# Sodonguyenly.net
KiCad netlist of a schematic drawn in Altium Designer
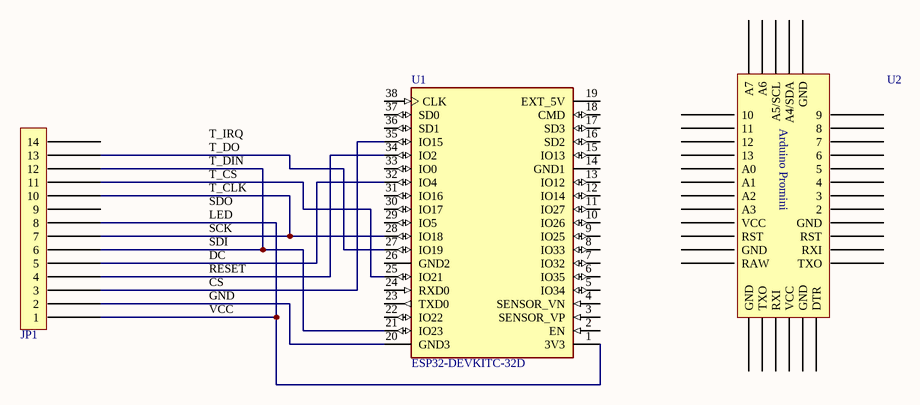
[diagram p0: Sodonguyenly.SchDoc]

(export (version "E")
  (design (tool "Eeschema 10.0.6"))
  (components
    (comp (ref "JP1")
      (value "JP")
      (footprint "Jumper 14x1 - duplicate")
      (libsource (lib "Thu vien jumper compoment") (part "Jumper 14x1"))
    )
    (comp (ref "U1")
      (value "ESP32-DEVKITC-32D")
      (footprint "MODULE_ESP32-DEVKITC-32D")
      (description "EVAL BOARD FOR ESP-WROOM-32")
      (fields (field (name "MF") "Espressif Systems"))
      (libsource (lib "ESP32-DEVKITC-32D") (part "ESP32-DEVKITC-32D"))
    )
    (comp (ref "U2")
      (value "Arduino Promini")
      (footprint "Arduino_Promini")
      (libsource (lib "Arduino_Promini") (part "Arduino Promini"))
    )
  )
  (nets
    (net (code "1") (name "Net-(U1-3V3)") (class "Default")
      (node (ref "JP1") (pin "1") (pinfunction "1_1") (pintype "passive"))
      (node (ref "JP1") (pin "8") (pinfunction "8_8") (pintype "passive"))
      (node (ref "U1") (pin "1") (pinfunction "3V3_1") (pintype "power_in"))
    )
    (net (code "2") (name "Net-(U1-GND3)") (class "Default")
      (node (ref "JP1") (pin "2") (pinfunction "2_2") (pintype "passive"))
      (node (ref "U1") (pin "20") (pinfunction "GND3_20") (pintype "power_in"))
    )
    (net (code "3") (name "Net-(U1-IO2)") (class "Default")
      (node (ref "JP1") (pin "4") (pinfunction "4_4") (pintype "passive"))
      (node (ref "U1") (pin "34") (pinfunction "IO2_34") (pintype "bidirectional"))
    )
    (net (code "4") (name "Net-(U1-IO4)") (class "Default")
      (node (ref "JP1") (pin "5") (pinfunction "5_5") (pintype "passive"))
      (node (ref "U1") (pin "32") (pinfunction "IO4_32") (pintype "bidirectional"))
    )
    (net (code "5") (name "Net-(U1-IO15)") (class "Default")
      (node (ref "JP1") (pin "3") (pinfunction "3_3") (pintype "passive"))
      (node (ref "U1") (pin "35") (pinfunction "IO15_35") (pintype "bidirectional"))
    )
    (net (code "6") (name "Net-(U1-IO18)") (class "Default")
      (node (ref "JP1") (pin "10") (pinfunction "10_10") (pintype "passive"))
      (node (ref "JP1") (pin "7") (pinfunction "7_7") (pintype "passive"))
      (node (ref "U1") (pin "28") (pinfunction "IO18_28") (pintype "bidirectional"))
    )
    (net (code "7") (name "Net-(U1-IO19)") (class "Default")
      (node (ref "JP1") (pin "13") (pinfunction "13_13") (pintype "passive"))
      (node (ref "U1") (pin "27") (pinfunction "IO19_27") (pintype "bidirectional"))
    )
    (net (code "8") (name "Net-(U1-IO21)") (class "Default")
      (node (ref "JP1") (pin "11") (pinfunction "11_11") (pintype "passive"))
      (node (ref "U1") (pin "25") (pinfunction "IO21_25") (pintype "bidirectional"))
    )
    (net (code "9") (name "Net-(U1-IO23)") (class "Default")
      (node (ref "JP1") (pin "12") (pinfunction "12_12") (pintype "passive"))
      (node (ref "JP1") (pin "6") (pinfunction "6_6") (pintype "passive"))
      (node (ref "U1") (pin "21") (pinfunction "IO23_21") (pintype "bidirectional"))
    )
    (net (code "10") (name "unconnected-(JP1-Pad9)") (class "Default")
      (node (ref "JP1") (pin "9") (pinfunction "9_9") (pintype "passive"))
    )
    (net (code "11") (name "unconnected-(JP1-Pad14)") (class "Default")
      (node (ref "JP1") (pin "14") (pinfunction "14_14") (pintype "passive"))
    )
    (net (code "12") (name "unconnected-(U1-CLK-Pad38)") (class "Default")
      (node (ref "U1") (pin "38") (pinfunction "CLK_38") (pintype "input"))
    )
    (net (code "13") (name "unconnected-(U1-CMD-Pad18)") (class "Default")
      (node (ref "U1") (pin "18") (pinfunction "CMD_18") (pintype "bidirectional"))
    )
    (net (code "14") (name "unconnected-(U1-EN-Pad2)") (class "Default")
      (node (ref "U1") (pin "2") (pinfunction "EN_2") (pintype "input"))
    )
    (net (code "15") (name "unconnected-(U1-EXT_5V-Pad19)") (class "Default")
      (node (ref "U1") (pin "19") (pinfunction "EXT_5V_19") (pintype "power_in"))
    )
    (net (code "16") (name "unconnected-(U1-GND1-Pad14)") (class "Default")
      (node (ref "U1") (pin "14") (pinfunction "GND1_14") (pintype "power_in"))
    )
    (net (code "17") (name "unconnected-(U1-GND2-Pad26)") (class "Default")
      (node (ref "U1") (pin "26") (pinfunction "GND2_26") (pintype "power_in"))
    )
    (net (code "18") (name "unconnected-(U1-IO0-Pad33)") (class "Default")
      (node (ref "U1") (pin "33") (pinfunction "IO0_33") (pintype "bidirectional"))
    )
    (net (code "19") (name "unconnected-(U1-IO5-Pad29)") (class "Default")
      (node (ref "U1") (pin "29") (pinfunction "IO5_29") (pintype "bidirectional"))
    )
    (net (code "20") (name "unconnected-(U1-IO12-Pad13)") (class "Default")
      (node (ref "U1") (pin "13") (pinfunction "IO12_13") (pintype "bidirectional"))
    )
    (net (code "21") (name "unconnected-(U1-IO13-Pad15)") (class "Default")
      (node (ref "U1") (pin "15") (pinfunction "IO13_15") (pintype "bidirectional"))
    )
    (net (code "22") (name "unconnected-(U1-IO14-Pad12)") (class "Default")
      (node (ref "U1") (pin "12") (pinfunction "IO14_12") (pintype "bidirectional"))
    )
    (net (code "23") (name "unconnected-(U1-IO16-Pad31)") (class "Default")
      (node (ref "U1") (pin "31") (pinfunction "IO16_31") (pintype "bidirectional"))
    )
    (net (code "24") (name "unconnected-(U1-IO17-Pad30)") (class "Default")
      (node (ref "U1") (pin "30") (pinfunction "IO17_30") (pintype "bidirectional"))
    )
    (net (code "25") (name "unconnected-(U1-IO22-Pad22)") (class "Default")
      (node (ref "U1") (pin "22") (pinfunction "IO22_22") (pintype "bidirectional"))
    )
    (net (code "26") (name "unconnected-(U1-IO25-Pad9)") (class "Default")
      (node (ref "U1") (pin "9") (pinfunction "IO25_9") (pintype "bidirectional"))
    )
    (net (code "27") (name "unconnected-(U1-IO26-Pad10)") (class "Default")
      (node (ref "U1") (pin "10") (pinfunction "IO26_10") (pintype "bidirectional"))
    )
    (net (code "28") (name "unconnected-(U1-IO27-Pad11)") (class "Default")
      (node (ref "U1") (pin "11") (pinfunction "IO27_11") (pintype "bidirectional"))
    )
    (net (code "29") (name "unconnected-(U1-IO32-Pad7)") (class "Default")
      (node (ref "U1") (pin "7") (pinfunction "IO32_7") (pintype "bidirectional"))
    )
    (net (code "30") (name "unconnected-(U1-IO33-Pad8)") (class "Default")
      (node (ref "U1") (pin "8") (pinfunction "IO33_8") (pintype "bidirectional"))
    )
    (net (code "31") (name "unconnected-(U1-IO34-Pad5)") (class "Default")
      (node (ref "U1") (pin "5") (pinfunction "IO34_5") (pintype "bidirectional"))
    )
    (net (code "32") (name "unconnected-(U1-IO35-Pad6)") (class "Default")
      (node (ref "U1") (pin "6") (pinfunction "IO35_6") (pintype "bidirectional"))
    )
    (net (code "33") (name "unconnected-(U1-RXD0-Pad24)") (class "Default")
      (node (ref "U1") (pin "24") (pinfunction "RXD0_24") (pintype "input"))
    )
    (net (code "34") (name "unconnected-(U1-SD0-Pad37)") (class "Default")
      (node (ref "U1") (pin "37") (pinfunction "SD0_37") (pintype "bidirectional"))
    )
    (net (code "35") (name "unconnected-(U1-SD1-Pad36)") (class "Default")
      (node (ref "U1") (pin "36") (pinfunction "SD1_36") (pintype "bidirectional"))
    )
    (net (code "36") (name "unconnected-(U1-SD2-Pad16)") (class "Default")
      (node (ref "U1") (pin "16") (pinfunction "SD2_16") (pintype "bidirectional"))
    )
    (net (code "37") (name "unconnected-(U1-SD3-Pad17)") (class "Default")
      (node (ref "U1") (pin "17") (pinfunction "SD3_17") (pintype "bidirectional"))
    )
    (net (code "38") (name "unconnected-(U1-SENSOR_VN-Pad4)") (class "Default")
      (node (ref "U1") (pin "4") (pinfunction "SENSOR_VN_4") (pintype "input"))
    )
    (net (code "39") (name "unconnected-(U1-SENSOR_VP-Pad3)") (class "Default")
      (node (ref "U1") (pin "3") (pinfunction "SENSOR_VP_3") (pintype "input"))
    )
    (net (code "40") (name "unconnected-(U1-TXD0-Pad23)") (class "Default")
      (node (ref "U1") (pin "23") (pinfunction "TXD0_23") (pintype "output"))
    )
    (net (code "41") (name "unconnected-(U2-2-Pad8)") (class "Default")
      (node (ref "U2") (pin "8") (pinfunction "2_8") (pintype "passive"))
    )
    (net (code "42") (name "unconnected-(U2-3-Pad7)") (class "Default")
      (node (ref "U2") (pin "7") (pinfunction "3_7") (pintype "passive"))
    )
    (net (code "43") (name "unconnected-(U2-4-Pad6)") (class "Default")
      (node (ref "U2") (pin "6") (pinfunction "4_6") (pintype "passive"))
    )
    (net (code "44") (name "unconnected-(U2-6-Pad4)") (class "Default")
      (node (ref "U2") (pin "4") (pinfunction "6_4") (pintype "passive"))
    )
    (net (code "45") (name "unconnected-(U2-7-Pad3)") (class "Default")
      (node (ref "U2") (pin "3") (pinfunction "7_3") (pintype "passive"))
    )
    (net (code "46") (name "unconnected-(U2-8-Pad2)") (class "Default")
      (node (ref "U2") (pin "2") (pinfunction "8_2") (pintype "passive"))
    )
    (net (code "47") (name "unconnected-(U2-9-Pad1)") (class "Default")
      (node (ref "U2") (pin "1") (pinfunction "9_1") (pintype "passive"))
    )
    (net (code "48") (name "unconnected-(U2-10-Pad30)") (class "Default")
      (node (ref "U2") (pin "30") (pinfunction "10_30") (pintype "passive"))
    )
    (net (code "49") (name "unconnected-(U2-11-Pad29)") (class "Default")
      (node (ref "U2") (pin "29") (pinfunction "11_29") (pintype "passive"))
    )
    (net (code "50") (name "unconnected-(U2-12-Pad28)") (class "Default")
      (node (ref "U2") (pin "28") (pinfunction "12_28") (pintype "passive"))
    )
    (net (code "51") (name "unconnected-(U2-13-Pad27)") (class "Default")
      (node (ref "U2") (pin "27") (pinfunction "13_27") (pintype "passive"))
    )
    (net (code "52") (name "unconnected-(U2-A0-Pad26)") (class "Default")
      (node (ref "U2") (pin "26") (pinfunction "A0_26") (pintype "passive"))
    )
    (net (code "53") (name "unconnected-(U2-A1-Pad25)") (class "Default")
      (node (ref "U2") (pin "25") (pinfunction "A1_25") (pintype "passive"))
    )
    (net (code "54") (name "unconnected-(U2-A2-Pad24)") (class "Default")
      (node (ref "U2") (pin "24") (pinfunction "A2_24") (pintype "passive"))
    )
    (net (code "55") (name "unconnected-(U2-A3-Pad23)") (class "Default")
      (node (ref "U2") (pin "23") (pinfunction "A3_23") (pintype "passive"))
    )
    (net (code "56") (name "unconnected-(U2-A4{slash}SDA-Pad34)") (class "Default")
      (node (ref "U2") (pin "34") (pinfunction "A4/SDA_34") (pintype "passive"))
    )
    (net (code "57") (name "unconnected-(U2-A5{slash}SCL-Pad33)") (class "Default")
      (node (ref "U2") (pin "33") (pinfunction "A5/SCL_33") (pintype "passive"))
    )
    (net (code "58") (name "unconnected-(U2-A6-Pad32)") (class "Default")
      (node (ref "U2") (pin "32") (pinfunction "A6_32") (pintype "passive"))
    )
    (net (code "59") (name "unconnected-(U2-A7-Pad31)") (class "Default")
      (node (ref "U2") (pin "31") (pinfunction "A7_31") (pintype "passive"))
    )
    (net (code "60") (name "unconnected-(U2-DTR-Pad13)") (class "Default")
      (node (ref "U2") (pin "13") (pinfunction "DTR_13") (pintype "passive"))
    )
    (net (code "61") (name "unconnected-(U2-GND-Pad9)") (class "Default")
      (node (ref "U2") (pin "9") (pinfunction "GND_9") (pintype "passive"))
    )
    (net (code "62") (name "unconnected-(U2-GND-Pad14)") (class "Default")
      (node (ref "U2") (pin "14") (pinfunction "GND_14") (pintype "passive"))
    )
    (net (code "63") (name "unconnected-(U2-GND-Pad18)") (class "Default")
      (node (ref "U2") (pin "18") (pinfunction "GND_18") (pintype "passive"))
    )
    (net (code "64") (name "unconnected-(U2-GND-Pad20)") (class "Default")
      (node (ref "U2") (pin "20") (pinfunction "GND_20") (pintype "passive"))
    )
    (net (code "65") (name "unconnected-(U2-GND-Pad35)") (class "Default")
      (node (ref "U2") (pin "35") (pinfunction "GND_35") (pintype "passive"))
    )
    (net (code "66") (name "unconnected-(U2-Pad5)") (class "Default")
      (node (ref "U2") (pin "5") (pinfunction "5_5") (pintype "passive"))
    )
    (net (code "67") (name "unconnected-(U2-RAW-Pad19)") (class "Default")
      (node (ref "U2") (pin "19") (pinfunction "RAW_19") (pintype "passive"))
    )
    (net (code "68") (name "unconnected-(U2-RST-Pad10)") (class "Default")
      (node (ref "U2") (pin "10") (pinfunction "RST_10") (pintype "passive"))
    )
    (net (code "69") (name "unconnected-(U2-RST-Pad21)") (class "Default")
      (node (ref "U2") (pin "21") (pinfunction "RST_21") (pintype "passive"))
    )
    (net (code "70") (name "unconnected-(U2-RXI-Pad11)") (class "Default")
      (node (ref "U2") (pin "11") (pinfunction "RXI_11") (pintype "passive"))
    )
    (net (code "71") (name "unconnected-(U2-RXI-Pad16)") (class "Default")
      (node (ref "U2") (pin "16") (pinfunction "RXI_16") (pintype "passive"))
    )
    (net (code "72") (name "unconnected-(U2-TXO-Pad12)") (class "Default")
      (node (ref "U2") (pin "12") (pinfunction "TXO_12") (pintype "passive"))
    )
    (net (code "73") (name "unconnected-(U2-TXO-Pad17)") (class "Default")
      (node (ref "U2") (pin "17") (pinfunction "TXO_17") (pintype "passive"))
    )
    (net (code "74") (name "unconnected-(U2-VCC-Pad15)") (class "Default")
      (node (ref "U2") (pin "15") (pinfunction "VCC_15") (pintype "passive"))
    )
    (net (code "75") (name "unconnected-(U2-VCC-Pad22)") (class "Default")
      (node (ref "U2") (pin "22") (pinfunction "VCC_22") (pintype "passive"))
    )
  )
)
